# 05_Amplifier.net
KiCad netlist of a schematic drawn in Altium Designer
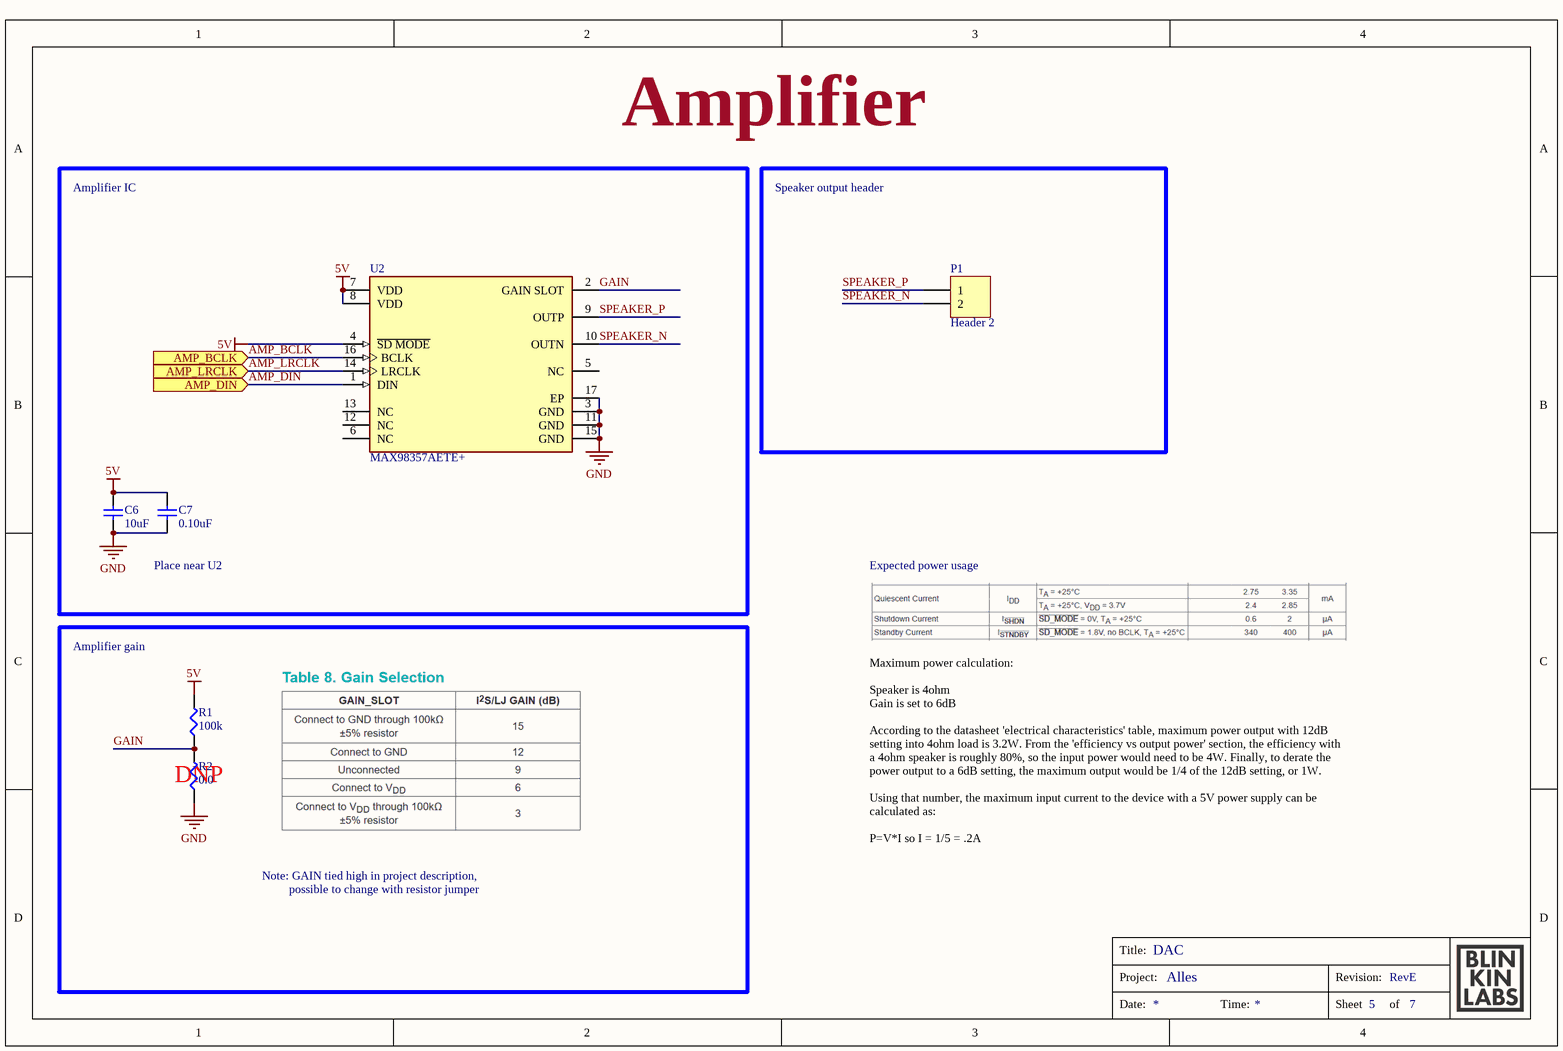
[diagram p0: [05] Amplifier.SchDoc]

(export (version "E")
  (design (tool "Eeschema 10.0.6"))
  (components
    (comp (ref "C6")
      (value "10uF")
      (footprint "CAPC1608X09L")
      (description "CAP CER 10UF 10V X5R 0603")
      (fields
        (field (name "PARTNUMBER") "GRM188R61A106KE69D")
        (field (name "DIGI-KEY PART NUMBER") "490-10474-1-ND")
      )
      (libsource (lib "cap_murata") (part "CAPACITOR"))
    )
    (comp (ref "C7")
      (value "0.10uF")
      (footprint "CAPC1005X06L")
      (description "CAP CER 0.1UF 10V X5R 0402")
      (fields
        (field (name "DIGI-KEY PART NUMBER") "490-10009-1-ND")
        (field (name "MANUFACTURER") "Murata Electronics North America")
      )
      (libsource (lib "cap_murata") (part "CAPACITOR"))
    )
    (comp (ref "P1")
      (value "Header 2")
      (footprint "HDR1X2")
      (description "Header, 2-Pin")
      (fields (field (name "PUBLISHER") "Altium Limited"))
      (libsource (lib "Miscellaneous Connectors") (part "Header 2"))
    )
    (comp (ref "R1")
      (value "100k")
      (footprint "ERJ2G(0402)_L")
      (description "RES SMD 100K OHM 5% 1/10W 0402")
      (fields (field (name "PARTNUMBER") "ERJ-2GEJ104X") (field (name "DIGI-KEY PART NUMBER") "P100KJCT-ND"))
      (libsource (lib "res_panasonic_erj_xls") (part "RESISTOR"))
    )
    (comp (ref "R2")
      (value "0.0")
      (footprint "ERJ2G(0402)_L")
      (description "RES SMD 0.0OHM JUMPER 1/10W 0402")
      (fields (field (name "PARTNUMBER") "ERJ-2GE0R00X") (field (name "DIGI-KEY PART NUMBER") "P0.0JCT-ND"))
      (libsource (lib "res_panasonic_erj_xls") (part "RESISTOR"))
    )
    (comp (ref "U2")
      (value "MAX98357AETE+")
      (footprint "FP-T1633-4-MFG")
      (description "IC AMP CLASS D MONO 3.2W 16TQFN")
      (libsource (lib "Altium Content Vault") (part "8462554c0df8f163c20def1e28525dd"))
    )
  )
  (nets
    (net (code "1") (name "/AMP_BCLK") (class "Default")
      (node (ref "U2") (pin "16") (pinfunction "BCLK_16") (pintype "input"))
    )
    (net (code "2") (name "/AMP_DIN") (class "Default")
      (node (ref "U2") (pin "1") (pinfunction "DIN_1") (pintype "input"))
    )
    (net (code "3") (name "/AMP_LRCLK") (class "Default")
      (node (ref "U2") (pin "14") (pinfunction "LRCLK_14") (pintype "input"))
    )
    (net (code "4") (name "/GAIN") (class "Default")
      (node (ref "R1") (pin "1") (pinfunction "1_1") (pintype "passive"))
      (node (ref "R2") (pin "2") (pinfunction "2_2") (pintype "passive"))
      (node (ref "U2") (pin "2") (pinfunction "GAIN_SLOT_2") (pintype "passive"))
    )
    (net (code "5") (name "/SPEAKER_N") (class "Default")
      (node (ref "P1") (pin "2") (pinfunction "2_2") (pintype "passive"))
      (node (ref "U2") (pin "10") (pinfunction "OUTN_10") (pintype "passive"))
    )
    (net (code "6") (name "/SPEAKER_P") (class "Default")
      (node (ref "P1") (pin "1") (pinfunction "1_1") (pintype "passive"))
      (node (ref "U2") (pin "9") (pinfunction "OUTP_9") (pintype "passive"))
    )
    (net (code "7") (name "5V") (class "Default")
      (node (ref "C6") (pin "1") (pinfunction "1_1") (pintype "passive"))
      (node (ref "C7") (pin "2") (pinfunction "2_2") (pintype "passive"))
      (node (ref "R1") (pin "2") (pinfunction "2_2") (pintype "passive"))
      (node (ref "U2") (pin "4") (pinfunction "~{SD_MODE}_4") (pintype "input"))
      (node (ref "U2") (pin "7") (pinfunction "VDD_7") (pintype "power_in"))
      (node (ref "U2") (pin "8") (pinfunction "VDD_8") (pintype "power_in"))
    )
    (net (code "8") (name "GND") (class "Default")
      (node (ref "C6") (pin "2") (pinfunction "2_2") (pintype "passive"))
      (node (ref "C7") (pin "1") (pinfunction "1_1") (pintype "passive"))
      (node (ref "R2") (pin "1") (pinfunction "1_1") (pintype "passive"))
      (node (ref "U2") (pin "11") (pinfunction "GND_11") (pintype "power_in"))
      (node (ref "U2") (pin "15") (pinfunction "GND_15") (pintype "power_in"))
      (node (ref "U2") (pin "17") (pinfunction "EP_17") (pintype "passive"))
      (node (ref "U2") (pin "3") (pinfunction "GND_3") (pintype "power_in"))
    )
    (net (code "9") (name "unconnected-(U2-NC-Pad5)") (class "Default")
      (node (ref "U2") (pin "5") (pinfunction "NC_5") (pintype "passive"))
    )
    (net (code "10") (name "unconnected-(U2-NC-Pad6)") (class "Default")
      (node (ref "U2") (pin "6") (pinfunction "NC_6") (pintype "passive"))
    )
    (net (code "11") (name "unconnected-(U2-NC-Pad12)") (class "Default")
      (node (ref "U2") (pin "12") (pinfunction "NC_12") (pintype "passive"))
    )
    (net (code "12") (name "unconnected-(U2-NC-Pad13)") (class "Default")
      (node (ref "U2") (pin "13") (pinfunction "NC_13") (pintype "passive"))
    )
  )
)
